# MainPCB_1P.net
KiCad netlist of a schematic drawn in EAGLE
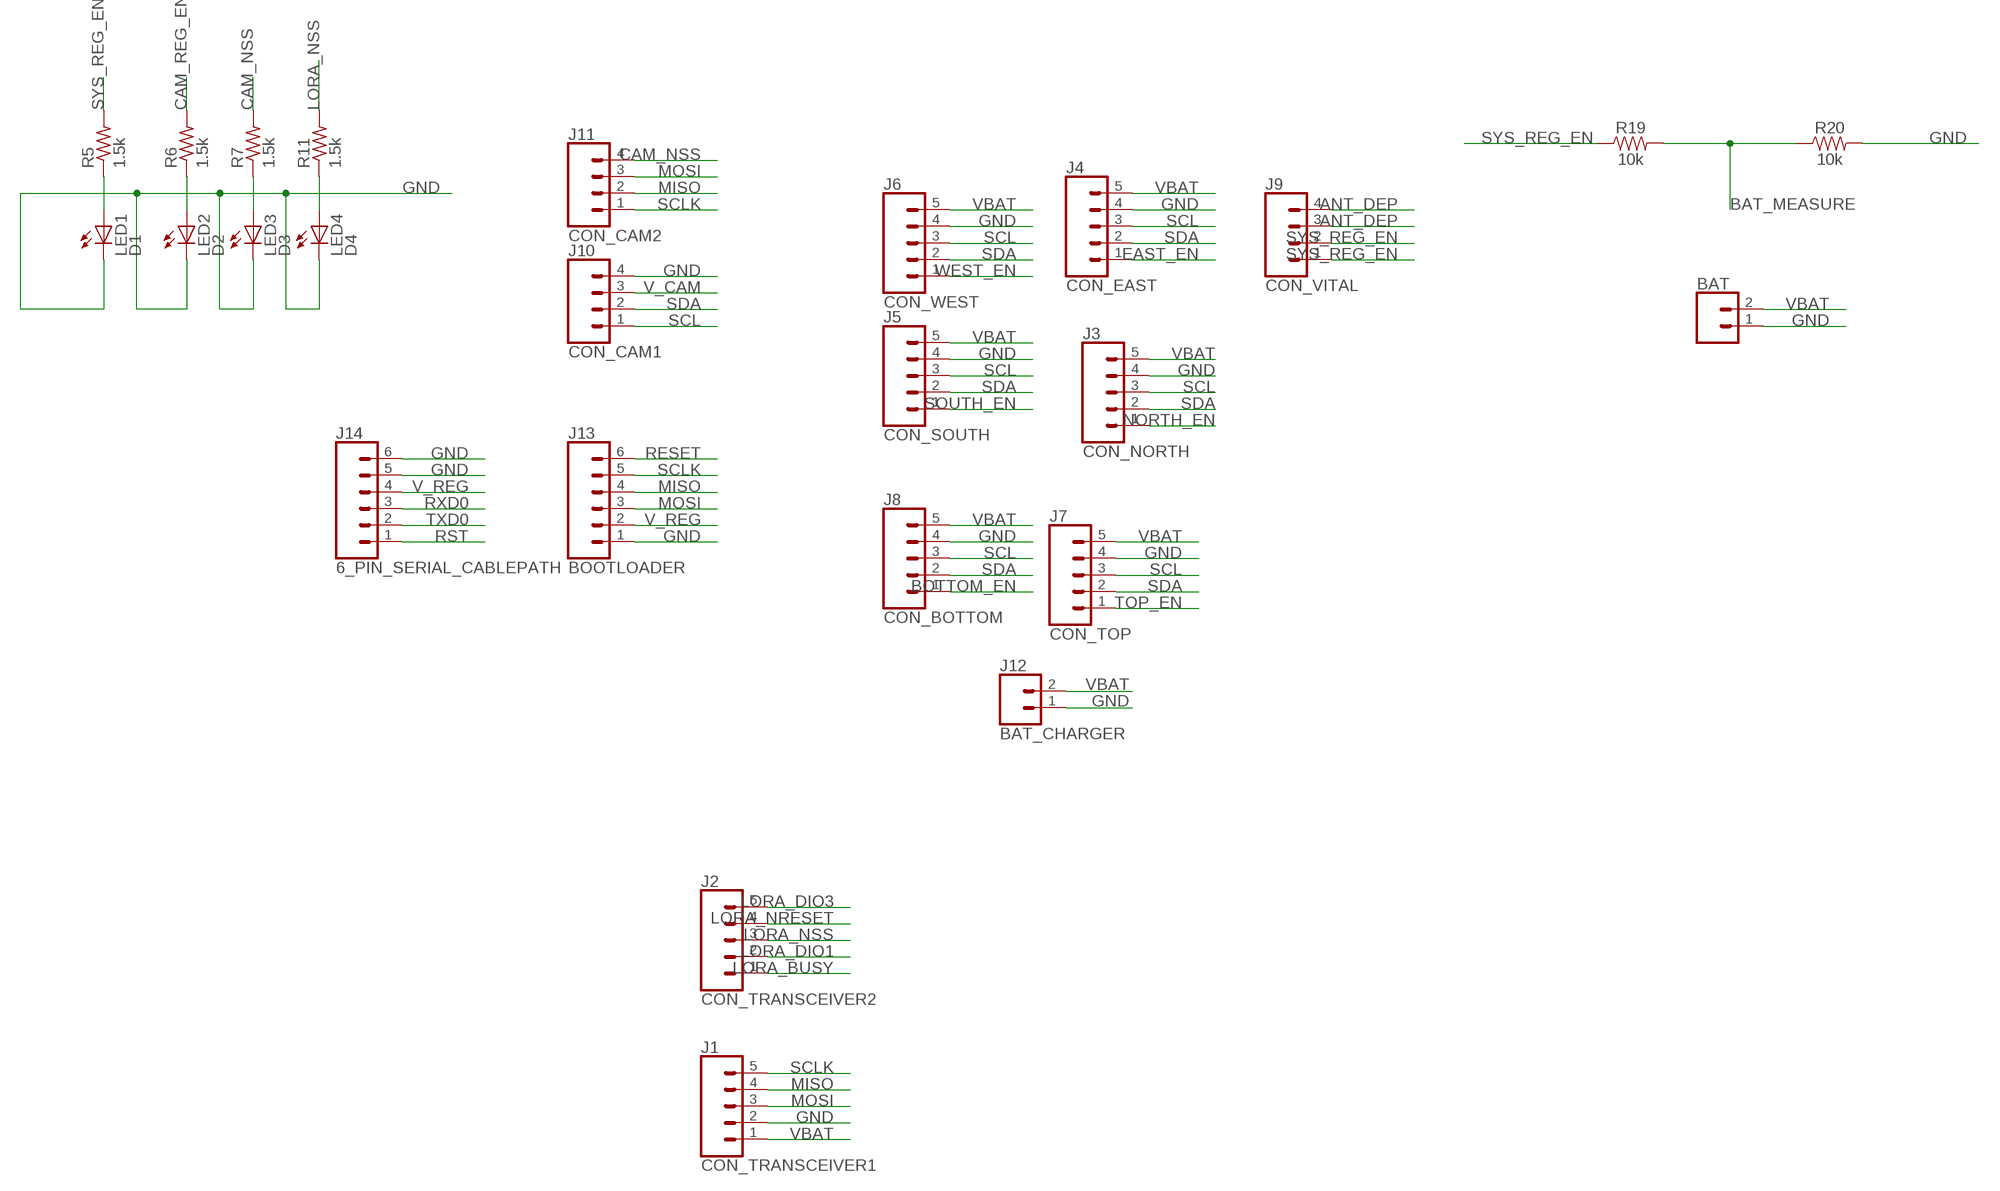
[diagram p0: schematic, sheet 1, part 1 of 2]
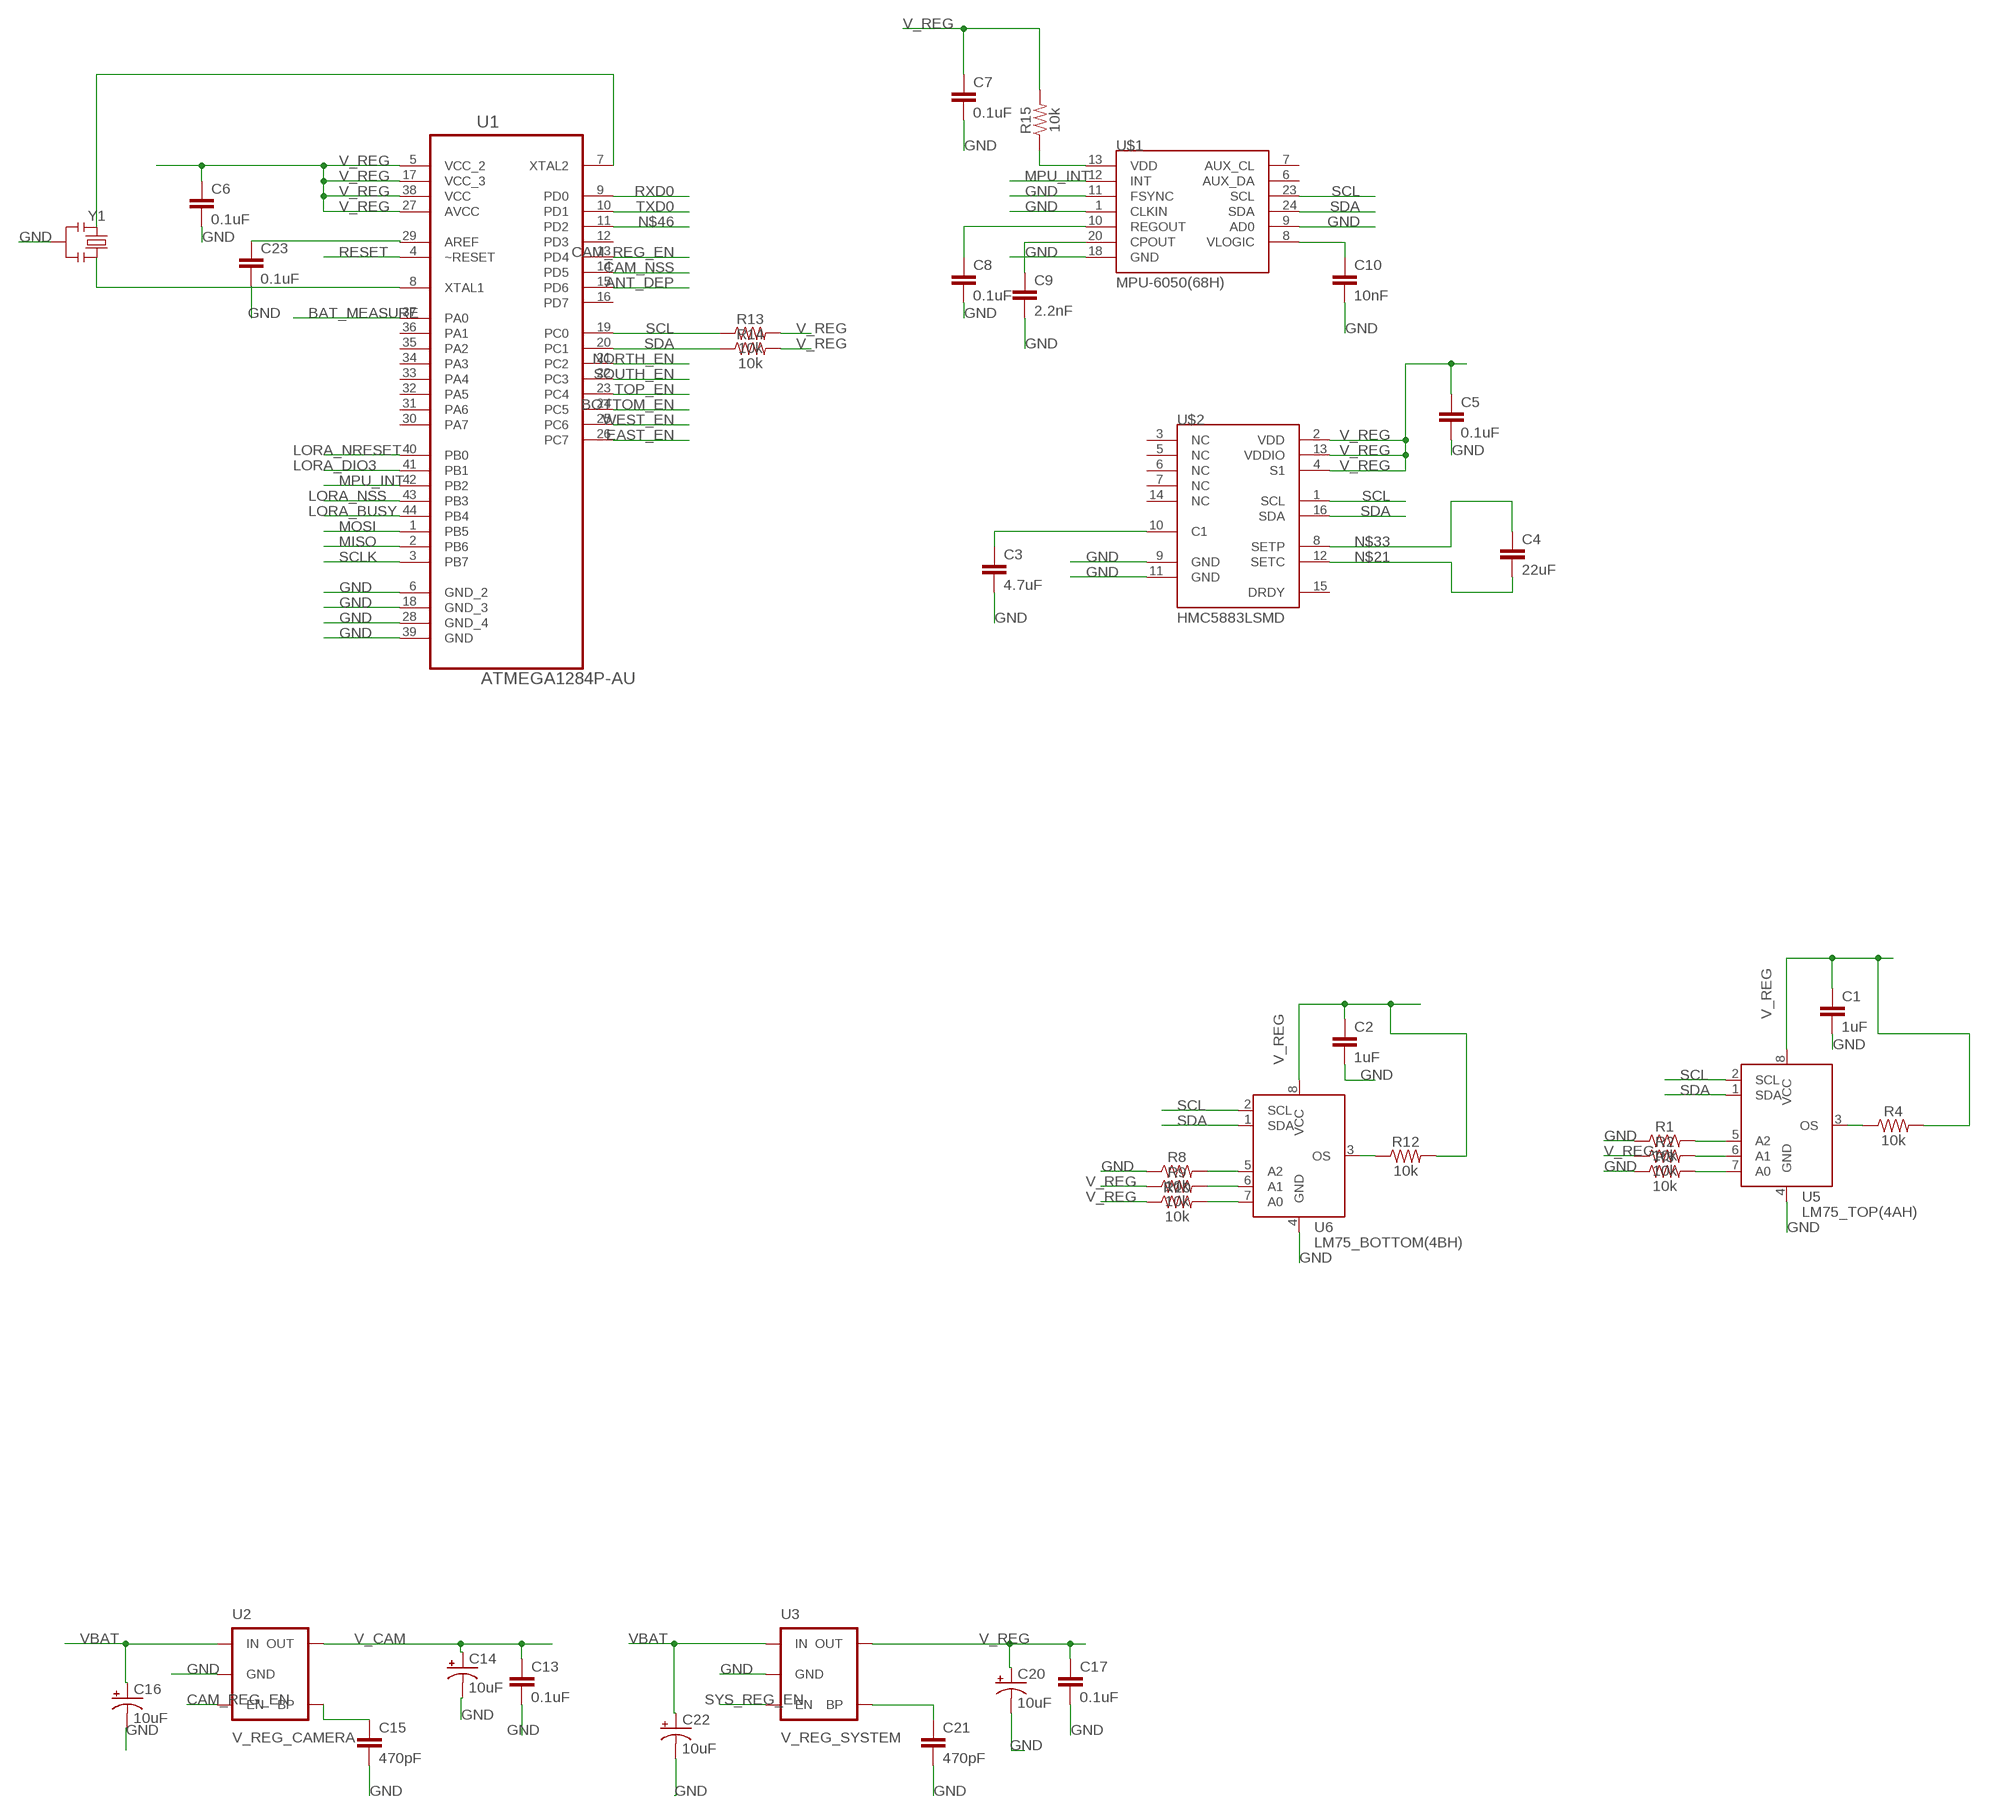
[diagram p1: schematic, sheet 1, part 2 of 2]

(export (version "E")
  (design (tool "Eeschema 10.0.6"))
  (components
    (comp (ref "BAT")
      (value "CONN_02")
      (footprint "eagle-import:1X02")
      (libsource (lib "eagle-import") (part "CONN_02"))
    )
    (comp (ref "C1")
      (value "1uF")
      (footprint "eagle-import:0603")
      (libsource (lib "eagle-import") (part "0.1UF-0603-25V-5%"))
    )
    (comp (ref "C2")
      (value "1uF")
      (footprint "eagle-import:0603")
      (libsource (lib "eagle-import") (part "0.1UF-0603-25V-5%"))
    )
    (comp (ref "C3")
      (value "4.7uF")
      (footprint "eagle-import:0603")
      (libsource (lib "eagle-import") (part "4.7UF-0603-35V-(20%)"))
    )
    (comp (ref "C4")
      (value "22uF")
      (footprint "eagle-import:0603")
      (libsource (lib "eagle-import") (part "22UF-0603-6.3V-20%"))
    )
    (comp (ref "C5")
      (value "0.1uF")
      (footprint "eagle-import:0603")
      (libsource (lib "eagle-import") (part "0.1UF-0603-100V-10%"))
    )
    (comp (ref "C6")
      (value "0.1uF")
      (footprint "eagle-import:0603")
      (libsource (lib "eagle-import") (part "0.1UF-0603-100V-10%"))
    )
    (comp (ref "C7")
      (value "0.1uF")
      (footprint "eagle-import:0603")
      (libsource (lib "eagle-import") (part "0.1UF-0603-100V-10%"))
    )
    (comp (ref "C8")
      (value "0.1uF")
      (footprint "eagle-import:0603")
      (libsource (lib "eagle-import") (part "0.1UF-0603-100V-10%"))
    )
    (comp (ref "C9")
      (value "2.2nF")
      (footprint "eagle-import:0603")
      (libsource (lib "eagle-import") (part "0.1UF-0603-100V-10%"))
    )
    (comp (ref "C10")
      (value "10nF")
      (footprint "eagle-import:0603")
      (libsource (lib "eagle-import") (part "0.1UF-0603-100V-10%"))
    )
    (comp (ref "C13")
      (value "0.1uF")
      (footprint "eagle-import:0603")
      (libsource (lib "eagle-import") (part "0.1UF-0603-100V-10%"))
    )
    (comp (ref "C14")
      (value "10uF")
      (footprint "eagle-import:0603-POLAR")
      (libsource (lib "eagle-import") (part "10UF-POLAR-0603-6.3V-20%(TANT)"))
    )
    (comp (ref "C15")
      (value "470pF")
      (footprint "eagle-import:0603")
      (libsource (lib "eagle-import") (part "0.1UF-0603-100V-10%"))
    )
    (comp (ref "C16")
      (value "10uF")
      (footprint "eagle-import:0603-POLAR")
      (libsource (lib "eagle-import") (part "10UF-POLAR-0603-6.3V-20%(TANT)"))
    )
    (comp (ref "C17")
      (value "0.1uF")
      (footprint "eagle-import:0603")
      (libsource (lib "eagle-import") (part "0.1UF-0603-100V-10%"))
    )
    (comp (ref "C20")
      (value "10uF")
      (footprint "eagle-import:0603-POLAR")
      (libsource (lib "eagle-import") (part "10UF-POLAR-0603-6.3V-20%(TANT)"))
    )
    (comp (ref "C21")
      (value "470pF")
      (footprint "eagle-import:0603")
      (libsource (lib "eagle-import") (part "0.1UF-0603-100V-10%"))
    )
    (comp (ref "C22")
      (value "10uF")
      (footprint "eagle-import:0603-POLAR")
      (libsource (lib "eagle-import") (part "10UF-POLAR-0603-6.3V-20%(TANT)"))
    )
    (comp (ref "C23")
      (value "0.1uF")
      (footprint "eagle-import:0603-CAP")
      (libsource (lib "eagle-import") (part "CAP0603-CAP"))
    )
    (comp (ref "J1")
      (value "CON_TRANSCEIVER1")
      (footprint "eagle-import:1X05_1.27MM")
      (libsource (lib "eagle-import") (part "CONN_051.27MM"))
    )
    (comp (ref "J2")
      (value "CON_TRANSCEIVER2")
      (footprint "eagle-import:1X05_1.27MM")
      (libsource (lib "eagle-import") (part "CONN_051.27MM"))
    )
    (comp (ref "J3")
      (value "CON_NORTH")
      (footprint "eagle-import:1X05_1.27MM")
      (libsource (lib "eagle-import") (part "CONN_051.27MM"))
    )
    (comp (ref "J4")
      (value "CON_EAST")
      (footprint "eagle-import:1X05_1.27MM")
      (libsource (lib "eagle-import") (part "CONN_051.27MM"))
    )
    (comp (ref "J5")
      (value "CON_SOUTH")
      (footprint "eagle-import:1X05_1.27MM")
      (libsource (lib "eagle-import") (part "CONN_051.27MM"))
    )
    (comp (ref "J6")
      (value "CON_WEST")
      (footprint "eagle-import:1X05_1.27MM")
      (libsource (lib "eagle-import") (part "CONN_051.27MM"))
    )
    (comp (ref "J7")
      (value "CON_TOP")
      (footprint "eagle-import:1X05_1.27MM")
      (libsource (lib "eagle-import") (part "CONN_051.27MM"))
    )
    (comp (ref "J8")
      (value "CON_BOTTOM")
      (footprint "eagle-import:1X05_1.27MM")
      (libsource (lib "eagle-import") (part "CONN_051.27MM"))
    )
    (comp (ref "J9")
      (value "CON_VITAL")
      (footprint "eagle-import:1X04_1.27MM")
      (libsource (lib "eagle-import") (part "CONN_041.27MM"))
    )
    (comp (ref "J10")
      (value "CON_CAM1")
      (footprint "eagle-import:1X04_1.27MM")
      (libsource (lib "eagle-import") (part "CONN_041.27MM"))
    )
    (comp (ref "J11")
      (value "CON_CAM2")
      (footprint "eagle-import:1X04_1.27MM")
      (libsource (lib "eagle-import") (part "CONN_041.27MM"))
    )
    (comp (ref "J12")
      (value "BAT_CHARGER")
      (footprint "eagle-import:1X02_NO_SILK")
      (libsource (lib "eagle-import") (part "SparkFun-Connectors_513_CONN_021X02_NO_SILK"))
    )
    (comp (ref "J13")
      (value "BOOTLOADER")
      (footprint "eagle-import:1X06_1.27MM")
      (libsource (lib "eagle-import") (part "CONN_061.27MM"))
    )
    (comp (ref "J14")
      (value "6_PIN_SERIAL_CABLEPATH")
      (footprint "eagle-import:1X06_1.27MM")
      (libsource (lib "eagle-import") (part "CONN_061.27MM"))
    )
    (comp (ref "LED1")
      (value "D1")
      (footprint "eagle-import:CHIP-LED0603")
      (libsource (lib "eagle-import") (part "LEDCHIP-LED0603"))
    )
    (comp (ref "LED2")
      (value "D2")
      (footprint "eagle-import:CHIP-LED0603")
      (libsource (lib "eagle-import") (part "LEDCHIP-LED0603"))
    )
    (comp (ref "LED3")
      (value "D3")
      (footprint "eagle-import:CHIP-LED0603")
      (libsource (lib "eagle-import") (part "LEDCHIP-LED0603"))
    )
    (comp (ref "LED4")
      (value "D4")
      (footprint "eagle-import:CHIP-LED0603")
      (libsource (lib "eagle-import") (part "LEDCHIP-LED0603"))
    )
    (comp (ref "R1")
      (value "10k")
      (footprint "eagle-import:0603")
      (libsource (lib "eagle-import") (part "RESISTOR0603"))
    )
    (comp (ref "R2")
      (value "10k")
      (footprint "eagle-import:0603")
      (libsource (lib "eagle-import") (part "RESISTOR0603"))
    )
    (comp (ref "R3")
      (value "10k")
      (footprint "eagle-import:0603")
      (libsource (lib "eagle-import") (part "RESISTOR0603"))
    )
    (comp (ref "R4")
      (value "10k")
      (footprint "eagle-import:0603")
      (libsource (lib "eagle-import") (part "RESISTOR0603"))
    )
    (comp (ref "R5")
      (value "1.5k")
      (footprint "eagle-import:R0603")
      (libsource (lib "eagle-import") (part "R-US_R0603"))
    )
    (comp (ref "R6")
      (value "1.5k")
      (footprint "eagle-import:R0603")
      (libsource (lib "eagle-import") (part "R-US_R0603"))
    )
    (comp (ref "R7")
      (value "1.5k")
      (footprint "eagle-import:R0603")
      (libsource (lib "eagle-import") (part "R-US_R0603"))
    )
    (comp (ref "R8")
      (value "10k")
      (footprint "eagle-import:0603")
      (libsource (lib "eagle-import") (part "RESISTOR0603"))
    )
    (comp (ref "R9")
      (value "10k")
      (footprint "eagle-import:0603")
      (libsource (lib "eagle-import") (part "RESISTOR0603"))
    )
    (comp (ref "R10")
      (value "10k")
      (footprint "eagle-import:0603")
      (libsource (lib "eagle-import") (part "RESISTOR0603"))
    )
    (comp (ref "R11")
      (value "1.5k")
      (footprint "eagle-import:R0603")
      (libsource (lib "eagle-import") (part "R-US_R0603"))
    )
    (comp (ref "R12")
      (value "10k")
      (footprint "eagle-import:0603")
      (libsource (lib "eagle-import") (part "RESISTOR0603"))
    )
    (comp (ref "R13")
      (value "10k")
      (footprint "eagle-import:0603")
      (libsource (lib "eagle-import") (part "RESISTOR0603"))
    )
    (comp (ref "R14")
      (value "10k")
      (footprint "eagle-import:0603")
      (libsource (lib "eagle-import") (part "RESISTOR0603"))
    )
    (comp (ref "R15")
      (value "10k")
      (footprint "eagle-import:0603")
      (libsource (lib "eagle-import") (part "RESISTOR0603"))
    )
    (comp (ref "R19")
      (value "10k")
      (footprint "eagle-import:0603")
      (libsource (lib "eagle-import") (part "1KOHM-0603-1/10W-1%"))
    )
    (comp (ref "R20")
      (value "10k")
      (footprint "eagle-import:0603")
      (libsource (lib "eagle-import") (part "1KOHM-0603-1/10W-1%"))
    )
    (comp (ref "U$1")
      (value "MPU-6050(68H)")
      (footprint "eagle-import:QFN-24-4MM2")
      (libsource (lib "eagle-import") (part "MPU-6050-1"))
    )
    (comp (ref "U$2")
      (value "HMC5883LSMD")
      (footprint "eagle-import:16LPCC")
      (libsource (lib "eagle-import") (part "HMC5883LSMD"))
    )
    (comp (ref "U1")
      (value "ATMEGA1284P-AU")
      (footprint "eagle-import:QFP80P1200X1200X120-44N")
      (fields (field (name "MF") "Microchip"))
      (libsource (lib "eagle-import") (part "ATMEGA1284P-AU"))
    )
    (comp (ref "U2")
      (value "V_REG_CAMERA")
      (footprint "eagle-import:SOT23-5")
      (libsource (lib "eagle-import") (part "V_REG_LDOSMD"))
    )
    (comp (ref "U3")
      (value "V_REG_SYSTEM")
      (footprint "eagle-import:SOT23-5")
      (libsource (lib "eagle-import") (part "V_REG_LDOSMD"))
    )
    (comp (ref "U5")
      (value "LM75_TOP(4AH)")
      (footprint "eagle-import:SOT505-1")
      (fields (field (name "MF") "NXP Semiconductors") (field (name "MP") "LM75B"))
      (libsource (lib "eagle-import") (part "LM75BDP"))
    )
    (comp (ref "U6")
      (value "LM75_BOTTOM(4BH)")
      (footprint "eagle-import:SOT505-1")
      (fields (field (name "MF") "NXP Semiconductors") (field (name "MP") "LM75B"))
      (libsource (lib "eagle-import") (part "LM75BDP"))
    )
    (comp (ref "Y1")
      (value "RESONATORSMD")
      (footprint "eagle-import:RESONATOR-SMD")
      (libsource (lib "eagle-import") (part "RESONATORSMD"))
    )
  )
  (nets
    (net (code "1") (name "/ANT_DEP") (class "Default")
      (node (ref "J9") (pin "3") (pinfunction "3_3") (pintype "passive"))
      (node (ref "J9") (pin "4") (pinfunction "4_4") (pintype "passive"))
      (node (ref "U1") (pin "15") (pinfunction "PD6_15") (pintype "bidirectional"))
    )
    (net (code "2") (name "/BAT_MEASURE") (class "Default")
      (node (ref "R19") (pin "2") (pinfunction "2_2") (pintype "passive"))
      (node (ref "R20") (pin "1") (pinfunction "1_1") (pintype "passive"))
      (node (ref "U1") (pin "37") (pinfunction "PA0_37") (pintype "bidirectional"))
    )
    (net (code "3") (name "/BOTTOM_EN") (class "Default")
      (node (ref "J8") (pin "1") (pinfunction "1_1") (pintype "passive"))
      (node (ref "U1") (pin "24") (pinfunction "PC5_24") (pintype "bidirectional"))
    )
    (net (code "4") (name "/CAM_NSS") (class "Default")
      (node (ref "J11") (pin "4") (pinfunction "4_4") (pintype "passive"))
      (node (ref "R7") (pin "2") (pinfunction "2_2") (pintype "passive"))
      (node (ref "U1") (pin "14") (pinfunction "PD5_14") (pintype "bidirectional"))
    )
    (net (code "5") (name "/CAM_REG_EN") (class "Default")
      (node (ref "R6") (pin "2") (pinfunction "2_2") (pintype "passive"))
      (node (ref "U1") (pin "13") (pinfunction "PD4_13") (pintype "bidirectional"))
      (node (ref "U2") (pin "3") (pinfunction "EN_3") (pintype "input"))
    )
    (net (code "6") (name "/EAST_EN") (class "Default")
      (node (ref "J4") (pin "1") (pinfunction "1_1") (pintype "passive"))
      (node (ref "U1") (pin "26") (pinfunction "PC7_26") (pintype "bidirectional"))
    )
    (net (code "7") (name "/GND") (class "Default")
      (node (ref "BAT") (pin "1") (pinfunction "1_1") (pintype "passive"))
      (node (ref "C1") (pin "2") (pinfunction "2_2") (pintype "passive"))
      (node (ref "C10") (pin "2") (pinfunction "2_2") (pintype "passive"))
      (node (ref "C13") (pin "2") (pinfunction "2_2") (pintype "passive"))
      (node (ref "C14") (pin "-") (pinfunction "-_-") (pintype "passive"))
      (node (ref "C15") (pin "2") (pinfunction "2_2") (pintype "passive"))
      (node (ref "C16") (pin "-") (pinfunction "-_-") (pintype "passive"))
      (node (ref "C17") (pin "2") (pinfunction "2_2") (pintype "passive"))
      (node (ref "C2") (pin "2") (pinfunction "2_2") (pintype "passive"))
      (node (ref "C20") (pin "-") (pinfunction "-_-") (pintype "passive"))
      (node (ref "C21") (pin "2") (pinfunction "2_2") (pintype "passive"))
      (node (ref "C22") (pin "-") (pinfunction "-_-") (pintype "passive"))
      (node (ref "C23") (pin "2") (pinfunction "2_2") (pintype "passive"))
      (node (ref "C3") (pin "2") (pinfunction "2_2") (pintype "passive"))
      (node (ref "C5") (pin "2") (pinfunction "2_2") (pintype "passive"))
      (node (ref "C6") (pin "2") (pinfunction "2_2") (pintype "passive"))
      (node (ref "C7") (pin "2") (pinfunction "2_2") (pintype "passive"))
      (node (ref "C8") (pin "2") (pinfunction "2_2") (pintype "passive"))
      (node (ref "C9") (pin "2") (pinfunction "2_2") (pintype "passive"))
      (node (ref "J1") (pin "2") (pinfunction "2_2") (pintype "passive"))
      (node (ref "J10") (pin "4") (pinfunction "4_4") (pintype "passive"))
      (node (ref "J12") (pin "1") (pinfunction "1_1") (pintype "passive"))
      (node (ref "J13") (pin "1") (pinfunction "1_1") (pintype "passive"))
      (node (ref "J14") (pin "5") (pinfunction "5_5") (pintype "passive"))
      (node (ref "J14") (pin "6") (pinfunction "6_6") (pintype "passive"))
      (node (ref "J3") (pin "4") (pinfunction "4_4") (pintype "passive"))
      (node (ref "J4") (pin "4") (pinfunction "4_4") (pintype "passive"))
      (node (ref "J5") (pin "4") (pinfunction "4_4") (pintype "passive"))
      (node (ref "J6") (pin "4") (pinfunction "4_4") (pintype "passive"))
      (node (ref "J7") (pin "4") (pinfunction "4_4") (pintype "passive"))
      (node (ref "J8") (pin "4") (pinfunction "4_4") (pintype "passive"))
      (node (ref "LED1") (pin "C") (pinfunction "C_C") (pintype "passive"))
      (node (ref "LED2") (pin "C") (pinfunction "C_C") (pintype "passive"))
      (node (ref "LED3") (pin "C") (pinfunction "C_C") (pintype "passive"))
      (node (ref "LED4") (pin "C") (pinfunction "C_C") (pintype "passive"))
      (node (ref "R1") (pin "1") (pinfunction "1_1") (pintype "passive"))
      (node (ref "R20") (pin "2") (pinfunction "2_2") (pintype "passive"))
      (node (ref "R3") (pin "1") (pinfunction "1_1") (pintype "passive"))
      (node (ref "R8") (pin "1") (pinfunction "1_1") (pintype "passive"))
      (node (ref "U$1") (pin "1") (pinfunction "CLKIN_1") (pintype "bidirectional"))
      (node (ref "U$1") (pin "11") (pinfunction "FSYNC_11") (pintype "bidirectional"))
      (node (ref "U$1") (pin "18") (pinfunction "GND_18") (pintype "bidirectional"))
      (node (ref "U$1") (pin "9") (pinfunction "AD0_9") (pintype "bidirectional"))
      (node (ref "U$2") (pin "11") (pinfunction "GND_11") (pintype "bidirectional"))
      (node (ref "U$2") (pin "9") (pinfunction "GND_9") (pintype "bidirectional"))
      (node (ref "U1") (pin "18") (pinfunction "GND_3_18") (pintype "passive"))
      (node (ref "U1") (pin "28") (pinfunction "GND_4_28") (pintype "passive"))
      (node (ref "U1") (pin "39") (pinfunction "GND_39") (pintype "passive"))
      (node (ref "U1") (pin "6") (pinfunction "GND_2_6") (pintype "passive"))
      (node (ref "U2") (pin "2") (pinfunction "GND_2") (pintype "input"))
      (node (ref "U3") (pin "2") (pinfunction "GND_2") (pintype "input"))
      (node (ref "U5") (pin "4") (pinfunction "GND_4") (pintype "bidirectional"))
      (node (ref "U6") (pin "4") (pinfunction "GND_4") (pintype "bidirectional"))
      (node (ref "Y1") (pin "2") (pinfunction "2_2") (pintype "passive"))
    )
    (net (code "8") (name "/LORA_BUSY") (class "Default")
      (node (ref "J2") (pin "1") (pinfunction "1_1") (pintype "passive"))
      (node (ref "U1") (pin "44") (pinfunction "PB4_44") (pintype "bidirectional"))
    )
    (net (code "9") (name "/LORA_DIO1") (class "Default")
      (node (ref "J2") (pin "2") (pinfunction "2_2") (pintype "passive"))
    )
    (net (code "10") (name "/LORA_DIO3") (class "Default")
      (node (ref "J2") (pin "5") (pinfunction "5_5") (pintype "passive"))
      (node (ref "U1") (pin "41") (pinfunction "PB1_41") (pintype "bidirectional"))
    )
    (net (code "11") (name "/LORA_NRESET") (class "Default")
      (node (ref "J2") (pin "4") (pinfunction "4_4") (pintype "passive"))
      (node (ref "U1") (pin "40") (pinfunction "PB0_40") (pintype "bidirectional"))
    )
    (net (code "12") (name "/LORA_NSS") (class "Default")
      (node (ref "J2") (pin "3") (pinfunction "3_3") (pintype "passive"))
      (node (ref "R11") (pin "2") (pinfunction "2_2") (pintype "passive"))
      (node (ref "U1") (pin "43") (pinfunction "PB3_43") (pintype "bidirectional"))
    )
    (net (code "13") (name "/MISO") (class "Default")
      (node (ref "J1") (pin "4") (pinfunction "4_4") (pintype "passive"))
      (node (ref "J11") (pin "2") (pinfunction "2_2") (pintype "passive"))
      (node (ref "J13") (pin "4") (pinfunction "4_4") (pintype "passive"))
      (node (ref "U1") (pin "2") (pinfunction "PB6_2") (pintype "bidirectional"))
    )
    (net (code "14") (name "/MOSI") (class "Default")
      (node (ref "J1") (pin "3") (pinfunction "3_3") (pintype "passive"))
      (node (ref "J11") (pin "3") (pinfunction "3_3") (pintype "passive"))
      (node (ref "J13") (pin "3") (pinfunction "3_3") (pintype "passive"))
      (node (ref "U1") (pin "1") (pinfunction "PB5_1") (pintype "bidirectional"))
    )
    (net (code "15") (name "/MPU_INT") (class "Default")
      (node (ref "U$1") (pin "12") (pinfunction "INT_12") (pintype "bidirectional"))
      (node (ref "U1") (pin "42") (pinfunction "PB2_42") (pintype "bidirectional"))
    )
    (net (code "16") (name "/N$21") (class "Default")
      (node (ref "C4") (pin "2") (pinfunction "2_2") (pintype "passive"))
      (node (ref "U$2") (pin "12") (pinfunction "SETC_12") (pintype "bidirectional"))
    )
    (net (code "17") (name "/N$33") (class "Default")
      (node (ref "C4") (pin "1") (pinfunction "1_1") (pintype "passive"))
      (node (ref "U$2") (pin "8") (pinfunction "SETP_8") (pintype "bidirectional"))
    )
    (net (code "18") (name "/N$46") (class "Default")
      (node (ref "U1") (pin "11") (pinfunction "PD2_11") (pintype "bidirectional"))
    )
    (net (code "19") (name "/NORTH_EN") (class "Default")
      (node (ref "J3") (pin "1") (pinfunction "1_1") (pintype "passive"))
      (node (ref "U1") (pin "21") (pinfunction "PC2_21") (pintype "bidirectional"))
    )
    (net (code "20") (name "/RESET") (class "Default")
      (node (ref "J13") (pin "6") (pinfunction "6_6") (pintype "passive"))
      (node (ref "U1") (pin "4") (pinfunction "~{RESET}_4") (pintype "input"))
    )
    (net (code "21") (name "/RST") (class "Default")
      (node (ref "J14") (pin "1") (pinfunction "1_1") (pintype "passive"))
    )
    (net (code "22") (name "/RXD0") (class "Default")
      (node (ref "J14") (pin "3") (pinfunction "3_3") (pintype "passive"))
      (node (ref "U1") (pin "9") (pinfunction "PD0_9") (pintype "bidirectional"))
    )
    (net (code "23") (name "/SCL") (class "Default")
      (node (ref "J10") (pin "1") (pinfunction "1_1") (pintype "passive"))
      (node (ref "J3") (pin "3") (pinfunction "3_3") (pintype "passive"))
      (node (ref "J4") (pin "3") (pinfunction "3_3") (pintype "passive"))
      (node (ref "J5") (pin "3") (pinfunction "3_3") (pintype "passive"))
      (node (ref "J6") (pin "3") (pinfunction "3_3") (pintype "passive"))
      (node (ref "J7") (pin "3") (pinfunction "3_3") (pintype "passive"))
      (node (ref "J8") (pin "3") (pinfunction "3_3") (pintype "passive"))
      (node (ref "R13") (pin "1") (pinfunction "1_1") (pintype "passive"))
      (node (ref "U$1") (pin "23") (pinfunction "SCL_23") (pintype "bidirectional"))
      (node (ref "U$2") (pin "1") (pinfunction "SCL_1") (pintype "bidirectional"))
      (node (ref "U1") (pin "19") (pinfunction "PC0_19") (pintype "bidirectional"))
      (node (ref "U5") (pin "2") (pinfunction "SCL_2") (pintype "bidirectional"))
      (node (ref "U6") (pin "2") (pinfunction "SCL_2") (pintype "bidirectional"))
    )
    (net (code "24") (name "/SCLK") (class "Default")
      (node (ref "J1") (pin "5") (pinfunction "5_5") (pintype "passive"))
      (node (ref "J11") (pin "1") (pinfunction "1_1") (pintype "passive"))
      (node (ref "J13") (pin "5") (pinfunction "5_5") (pintype "passive"))
      (node (ref "U1") (pin "3") (pinfunction "PB7_3") (pintype "bidirectional"))
    )
    (net (code "25") (name "/SDA") (class "Default")
      (node (ref "J10") (pin "2") (pinfunction "2_2") (pintype "passive"))
      (node (ref "J3") (pin "2") (pinfunction "2_2") (pintype "passive"))
      (node (ref "J4") (pin "2") (pinfunction "2_2") (pintype "passive"))
      (node (ref "J5") (pin "2") (pinfunction "2_2") (pintype "passive"))
      (node (ref "J6") (pin "2") (pinfunction "2_2") (pintype "passive"))
      (node (ref "J7") (pin "2") (pinfunction "2_2") (pintype "passive"))
      (node (ref "J8") (pin "2") (pinfunction "2_2") (pintype "passive"))
      (node (ref "R14") (pin "1") (pinfunction "1_1") (pintype "passive"))
      (node (ref "U$1") (pin "24") (pinfunction "SDA_24") (pintype "bidirectional"))
      (node (ref "U$2") (pin "16") (pinfunction "SDA_16") (pintype "bidirectional"))
      (node (ref "U1") (pin "20") (pinfunction "PC1_20") (pintype "bidirectional"))
      (node (ref "U5") (pin "1") (pinfunction "SDA_1") (pintype "bidirectional"))
      (node (ref "U6") (pin "1") (pinfunction "SDA_1") (pintype "bidirectional"))
    )
    (net (code "26") (name "/SOUTH_EN") (class "Default")
      (node (ref "J5") (pin "1") (pinfunction "1_1") (pintype "passive"))
      (node (ref "U1") (pin "22") (pinfunction "PC3_22") (pintype "bidirectional"))
    )
    (net (code "27") (name "/SYS_REG_EN") (class "Default")
      (node (ref "J9") (pin "1") (pinfunction "1_1") (pintype "passive"))
      (node (ref "J9") (pin "2") (pinfunction "2_2") (pintype "passive"))
      (node (ref "R19") (pin "1") (pinfunction "1_1") (pintype "passive"))
      (node (ref "R5") (pin "2") (pinfunction "2_2") (pintype "passive"))
      (node (ref "U3") (pin "3") (pinfunction "EN_3") (pintype "input"))
    )
    (net (code "28") (name "/TOP_EN") (class "Default")
      (node (ref "J7") (pin "1") (pinfunction "1_1") (pintype "passive"))
      (node (ref "U1") (pin "23") (pinfunction "PC4_23") (pintype "bidirectional"))
    )
    (net (code "29") (name "/TXD0") (class "Default")
      (node (ref "J14") (pin "2") (pinfunction "2_2") (pintype "passive"))
      (node (ref "U1") (pin "10") (pinfunction "PD1_10") (pintype "bidirectional"))
    )
    (net (code "30") (name "/VBAT") (class "Default")
      (node (ref "BAT") (pin "2") (pinfunction "2_2") (pintype "passive"))
      (node (ref "C16") (pin "+") (pinfunction "+_+") (pintype "passive"))
      (node (ref "C22") (pin "+") (pinfunction "+_+") (pintype "passive"))
      (node (ref "J1") (pin "1") (pinfunction "1_1") (pintype "passive"))
      (node (ref "J12") (pin "2") (pinfunction "2_2") (pintype "passive"))
      (node (ref "J3") (pin "5") (pinfunction "5_5") (pintype "passive"))
      (node (ref "J4") (pin "5") (pinfunction "5_5") (pintype "passive"))
      (node (ref "J5") (pin "5") (pinfunction "5_5") (pintype "passive"))
      (node (ref "J6") (pin "5") (pinfunction "5_5") (pintype "passive"))
      (node (ref "J7") (pin "5") (pinfunction "5_5") (pintype "passive"))
      (node (ref "J8") (pin "5") (pinfunction "5_5") (pintype "passive"))
      (node (ref "U2") (pin "1") (pinfunction "IN_1") (pintype "input"))
      (node (ref "U3") (pin "1") (pinfunction "IN_1") (pintype "input"))
    )
    (net (code "31") (name "/V_CAM") (class "Default")
      (node (ref "C13") (pin "1") (pinfunction "1_1") (pintype "passive"))
      (node (ref "C14") (pin "+") (pinfunction "+_+") (pintype "passive"))
      (node (ref "J10") (pin "3") (pinfunction "3_3") (pintype "passive"))
      (node (ref "U2") (pin "5") (pinfunction "OUT_5") (pintype "passive"))
    )
    (net (code "32") (name "/V_REG") (class "Default")
      (node (ref "C1") (pin "1") (pinfunction "1_1") (pintype "passive"))
      (node (ref "C17") (pin "1") (pinfunction "1_1") (pintype "passive"))
      (node (ref "C2") (pin "1") (pinfunction "1_1") (pintype "passive"))
      (node (ref "C20") (pin "+") (pinfunction "+_+") (pintype "passive"))
      (node (ref "C5") (pin "1") (pinfunction "1_1") (pintype "passive"))
      (node (ref "C6") (pin "1") (pinfunction "1_1") (pintype "passive"))
      (node (ref "C7") (pin "1") (pinfunction "1_1") (pintype "passive"))
      (node (ref "J13") (pin "2") (pinfunction "2_2") (pintype "passive"))
      (node (ref "J14") (pin "4") (pinfunction "4_4") (pintype "passive"))
      (node (ref "R10") (pin "1") (pinfunction "1_1") (pintype "passive"))
      (node (ref "R12") (pin "2") (pinfunction "2_2") (pintype "passive"))
      (node (ref "R13") (pin "2") (pinfunction "2_2") (pintype "passive"))
      (node (ref "R14") (pin "2") (pinfunction "2_2") (pintype "passive"))
      (node (ref "R15") (pin "2") (pinfunction "2_2") (pintype "passive"))
      (node (ref "R2") (pin "1") (pinfunction "1_1") (pintype "passive"))
      (node (ref "R4") (pin "2") (pinfunction "2_2") (pintype "passive"))
      (node (ref "R9") (pin "1") (pinfunction "1_1") (pintype "passive"))
      (node (ref "U$2") (pin "13") (pinfunction "VDDIO_13") (pintype "bidirectional"))
      (node (ref "U$2") (pin "2") (pinfunction "VDD_2") (pintype "bidirectional"))
      (node (ref "U$2") (pin "4") (pinfunction "S1_4") (pintype "bidirectional"))
      (node (ref "U1") (pin "17") (pinfunction "VCC_3_17") (pintype "power_in"))
      (node (ref "U1") (pin "27") (pinfunction "AVCC_27") (pintype "power_in"))
      (node (ref "U1") (pin "38") (pinfunction "VCC_38") (pintype "power_in"))
      (node (ref "U1") (pin "5") (pinfunction "VCC_2_5") (pintype "power_in"))
      (node (ref "U3") (pin "5") (pinfunction "OUT_5") (pintype "passive"))
      (node (ref "U5") (pin "8") (pinfunction "VCC_8") (pintype "power_in"))
      (node (ref "U6") (pin "8") (pinfunction "VCC_8") (pintype "power_in"))
    )
    (net (code "33") (name "/WEST_EN") (class "Default")
      (node (ref "J6") (pin "1") (pinfunction "1_1") (pintype "passive"))
      (node (ref "U1") (pin "25") (pinfunction "PC6_25") (pintype "bidirectional"))
    )
    (net (code "34") (name "Net-(LED1-PadA)") (class "Default")
      (node (ref "LED1") (pin "A") (pinfunction "A_A") (pintype "passive"))
      (node (ref "R5") (pin "1") (pinfunction "1_1") (pintype "passive"))
    )
    (net (code "35") (name "Net-(LED2-PadA)") (class "Default")
      (node (ref "LED2") (pin "A") (pinfunction "A_A") (pintype "passive"))
      (node (ref "R6") (pin "1") (pinfunction "1_1") (pintype "passive"))
    )
    (net (code "36") (name "Net-(LED3-PadA)") (class "Default")
      (node (ref "LED3") (pin "A") (pinfunction "A_A") (pintype "passive"))
      (node (ref "R7") (pin "1") (pinfunction "1_1") (pintype "passive"))
    )
    (net (code "37") (name "Net-(LED4-PadA)") (class "Default")
      (node (ref "LED4") (pin "A") (pinfunction "A_A") (pintype "passive"))
      (node (ref "R11") (pin "1") (pinfunction "1_1") (pintype "passive"))
    )
    (net (code "38") (name "Net-(U$1-CPOUT)") (class "Default")
      (node (ref "C9") (pin "1") (pinfunction "1_1") (pintype "passive"))
      (node (ref "U$1") (pin "20") (pinfunction "CPOUT_20") (pintype "bidirectional"))
    )
    (net (code "39") (name "Net-(U$1-REGOUT)") (class "Default")
      (node (ref "C8") (pin "1") (pinfunction "1_1") (pintype "passive"))
      (node (ref "U$1") (pin "10") (pinfunction "REGOUT_10") (pintype "bidirectional"))
    )
    (net (code "40") (name "Net-(U$1-VDD)") (class "Default")
      (node (ref "R15") (pin "1") (pinfunction "1_1") (pintype "passive"))
      (node (ref "U$1") (pin "13") (pinfunction "VDD_13") (pintype "bidirectional"))
    )
    (net (code "41") (name "Net-(U$1-VLOGIC)") (class "Default")
      (node (ref "C10") (pin "1") (pinfunction "1_1") (pintype "passive"))
      (node (ref "U$1") (pin "8") (pinfunction "VLOGIC_8") (pintype "bidirectional"))
    )
    (net (code "42") (name "Net-(U$2-C1)") (class "Default")
      (node (ref "C3") (pin "1") (pinfunction "1_1") (pintype "passive"))
      (node (ref "U$2") (pin "10") (pinfunction "C1_10") (pintype "bidirectional"))
    )
    (net (code "43") (name "Net-(U1-AREF)") (class "Default")
      (node (ref "C23") (pin "1") (pinfunction "1_1") (pintype "passive"))
      (node (ref "U1") (pin "29") (pinfunction "AREF_29") (pintype "input"))
    )
    (net (code "44") (name "Net-(U1-XTAL1)") (class "Default")
      (node (ref "U1") (pin "8") (pinfunction "XTAL1_8") (pintype "input"))
      (node (ref "Y1") (pin "3") (pinfunction "3_3") (pintype "passive"))
    )
    (net (code "45") (name "Net-(U1-XTAL2)") (class "Default")
      (node (ref "U1") (pin "7") (pinfunction "XTAL2_7") (pintype "output"))
      (node (ref "Y1") (pin "1") (pinfunction "1_1") (pintype "passive"))
    )
    (net (code "46") (name "Net-(U2-BP)") (class "Default")
      (node (ref "C15") (pin "1") (pinfunction "1_1") (pintype "passive"))
      (node (ref "U2") (pin "4") (pinfunction "BP_4") (pintype "input"))
    )
    (net (code "47") (name "Net-(U3-BP)") (class "Default")
      (node (ref "C21") (pin "1") (pinfunction "1_1") (pintype "passive"))
      (node (ref "U3") (pin "4") (pinfunction "BP_4") (pintype "input"))
    )
    (net (code "48") (name "Net-(U5-A0)") (class "Default")
      (node (ref "R3") (pin "2") (pinfunction "2_2") (pintype "passive"))
      (node (ref "U5") (pin "7") (pinfunction "A0_7") (pintype "input"))
    )
    (net (code "49") (name "Net-(U5-A1)") (class "Default")
      (node (ref "R2") (pin "2") (pinfunction "2_2") (pintype "passive"))
      (node (ref "U5") (pin "6") (pinfunction "A1_6") (pintype "input"))
    )
    (net (code "50") (name "Net-(U5-A2)") (class "Default")
      (node (ref "R1") (pin "2") (pinfunction "2_2") (pintype "passive"))
      (node (ref "U5") (pin "5") (pinfunction "A2_5") (pintype "input"))
    )
    (net (code "51") (name "Net-(U5-OS)") (class "Default")
      (node (ref "R4") (pin "1") (pinfunction "1_1") (pintype "passive"))
      (node (ref "U5") (pin "3") (pinfunction "OS_3") (pintype "output"))
    )
    (net (code "52") (name "Net-(U6-A0)") (class "Default")
      (node (ref "R10") (pin "2") (pinfunction "2_2") (pintype "passive"))
      (node (ref "U6") (pin "7") (pinfunction "A0_7") (pintype "input"))
    )
    (net (code "53") (name "Net-(U6-A1)") (class "Default")
      (node (ref "R9") (pin "2") (pinfunction "2_2") (pintype "passive"))
      (node (ref "U6") (pin "6") (pinfunction "A1_6") (pintype "input"))
    )
    (net (code "54") (name "Net-(U6-A2)") (class "Default")
      (node (ref "R8") (pin "2") (pinfunction "2_2") (pintype "passive"))
      (node (ref "U6") (pin "5") (pinfunction "A2_5") (pintype "input"))
    )
    (net (code "55") (name "Net-(U6-OS)") (class "Default")
      (node (ref "R12") (pin "1") (pinfunction "1_1") (pintype "passive"))
      (node (ref "U6") (pin "3") (pinfunction "OS_3") (pintype "output"))
    )
    (net (code "56") (name "unconnected-(U$1-AUX_CL-Pad7)") (class "Default")
      (node (ref "U$1") (pin "7") (pinfunction "AUX_CL_7") (pintype "bidirectional"))
    )
    (net (code "57") (name "unconnected-(U$1-AUX_DA-Pad6)") (class "Default")
      (node (ref "U$1") (pin "6") (pinfunction "AUX_DA_6") (pintype "bidirectional"))
    )
    (net (code "58") (name "unconnected-(U$2-DRDY-Pad15)") (class "Default")
      (node (ref "U$2") (pin "15") (pinfunction "DRDY_15") (pintype "bidirectional"))
    )
    (net (code "59") (name "unconnected-(U$2-NC-Pad3)") (class "Default")
      (node (ref "U$2") (pin "3") (pinfunction "NC_3") (pintype "bidirectional"))
    )
    (net (code "60") (name "unconnected-(U$2-NC-Pad5)") (class "Default")
      (node (ref "U$2") (pin "5") (pinfunction "NC_5") (pintype "bidirectional"))
    )
    (net (code "61") (name "unconnected-(U$2-NC-Pad6)") (class "Default")
      (node (ref "U$2") (pin "6") (pinfunction "NC_6") (pintype "bidirectional"))
    )
    (net (code "62") (name "unconnected-(U$2-NC-Pad7)") (class "Default")
      (node (ref "U$2") (pin "7") (pinfunction "NC_7") (pintype "bidirectional"))
    )
    (net (code "63") (name "unconnected-(U$2-NC-Pad14)") (class "Default")
      (node (ref "U$2") (pin "14") (pinfunction "NC_14") (pintype "bidirectional"))
    )
    (net (code "64") (name "unconnected-(U1-PA1-Pad36)") (class "Default")
      (node (ref "U1") (pin "36") (pinfunction "PA1_36") (pintype "bidirectional"))
    )
    (net (code "65") (name "unconnected-(U1-PA2-Pad35)") (class "Default")
      (node (ref "U1") (pin "35") (pinfunction "PA2_35") (pintype "bidirectional"))
    )
    (net (code "66") (name "unconnected-(U1-PA3-Pad34)") (class "Default")
      (node (ref "U1") (pin "34") (pinfunction "PA3_34") (pintype "bidirectional"))
    )
    (net (code "67") (name "unconnected-(U1-PA4-Pad33)") (class "Default")
      (node (ref "U1") (pin "33") (pinfunction "PA4_33") (pintype "bidirectional"))
    )
    (net (code "68") (name "unconnected-(U1-PA5-Pad32)") (class "Default")
      (node (ref "U1") (pin "32") (pinfunction "PA5_32") (pintype "bidirectional"))
    )
    (net (code "69") (name "unconnected-(U1-PA6-Pad31)") (class "Default")
      (node (ref "U1") (pin "31") (pinfunction "PA6_31") (pintype "bidirectional"))
    )
    (net (code "70") (name "unconnected-(U1-PA7-Pad30)") (class "Default")
      (node (ref "U1") (pin "30") (pinfunction "PA7_30") (pintype "bidirectional"))
    )
    (net (code "71") (name "unconnected-(U1-PD3-Pad12)") (class "Default")
      (node (ref "U1") (pin "12") (pinfunction "PD3_12") (pintype "bidirectional"))
    )
    (net (code "72") (name "unconnected-(U1-PD7-Pad16)") (class "Default")
      (node (ref "U1") (pin "16") (pinfunction "PD7_16") (pintype "bidirectional"))
    )
  )
)
